# ExpansionHub.net
KiCad netlist of a schematic drawn in EAGLE
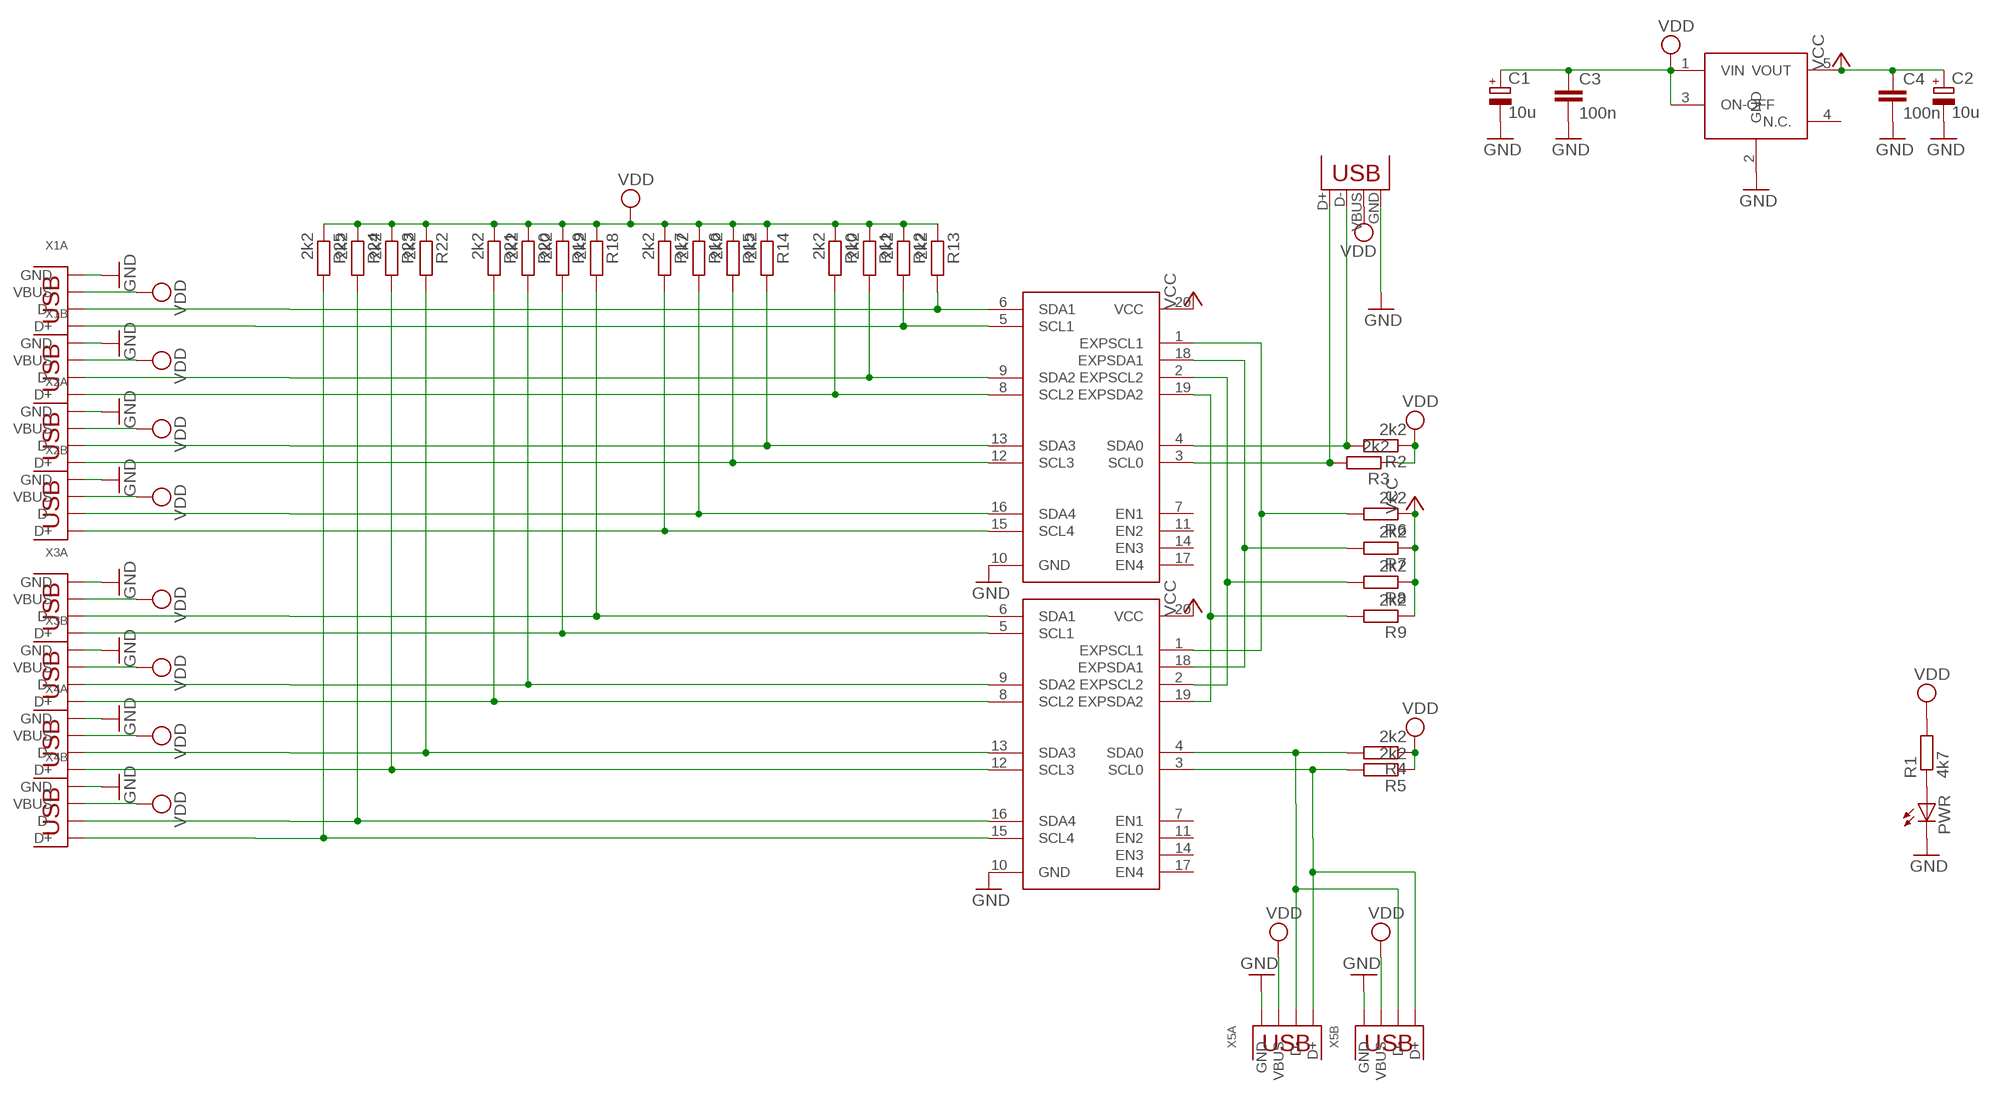
[diagram p0: schematic, sheet 1]

(export (version "E")
  (design (tool "Eeschema 10.0.6"))
  (components
    (comp (ref "C1")
      (value "10u")
      (footprint "eagle-import:A_3216-18W")
      (libsource (lib "eagle-import") (part "CPOL-EUA/3216-18W"))
    )
    (comp (ref "C2")
      (value "10u")
      (footprint "eagle-import:A_3216-18W")
      (libsource (lib "eagle-import") (part "CPOL-EUA/3216-18W"))
    )
    (comp (ref "C3")
      (value "100n")
      (footprint "eagle-import:C0805")
      (libsource (lib "eagle-import") (part "C-EUC0805"))
    )
    (comp (ref "C4")
      (value "100n")
      (footprint "eagle-import:C0805")
      (libsource (lib "eagle-import") (part "C-EUC0805"))
    )
    (comp (ref "IC1")
      (value "PCA9518")
      (footprint "eagle-import:TSSOP20")
      (libsource (lib "eagle-import") (part "PCA9518"))
    )
    (comp (ref "IC2")
      (value "PCA9518")
      (footprint "eagle-import:TSSOP20")
      (libsource (lib "eagle-import") (part "PCA9518"))
    )
    (comp (ref "PWR")
      (value "LED3MM")
      (footprint "eagle-import:LED3MM")
      (libsource (lib "eagle-import") (part "LED3MM"))
    )
    (comp (ref "R1")
      (value "4k7")
      (footprint "eagle-import:R0805W")
      (libsource (lib "eagle-import") (part "R-EU_R0805W"))
    )
    (comp (ref "R2")
      (value "2k2")
      (footprint "eagle-import:R0805")
      (libsource (lib "eagle-import") (part "R-EU_R0805"))
    )
    (comp (ref "R3")
      (value "2k2")
      (footprint "eagle-import:R0805")
      (libsource (lib "eagle-import") (part "R-EU_R0805"))
    )
    (comp (ref "R4")
      (value "2k2")
      (footprint "eagle-import:R0805")
      (libsource (lib "eagle-import") (part "R-EU_R0805"))
    )
    (comp (ref "R5")
      (value "2k2")
      (footprint "eagle-import:R0805")
      (libsource (lib "eagle-import") (part "R-EU_R0805"))
    )
    (comp (ref "R6")
      (value "2k2")
      (footprint "eagle-import:R0805")
      (libsource (lib "eagle-import") (part "R-EU_R0805"))
    )
    (comp (ref "R7")
      (value "2k2")
      (footprint "eagle-import:R0805")
      (libsource (lib "eagle-import") (part "R-EU_R0805"))
    )
    (comp (ref "R8")
      (value "2k2")
      (footprint "eagle-import:R0805")
      (libsource (lib "eagle-import") (part "R-EU_R0805"))
    )
    (comp (ref "R9")
      (value "2k2")
      (footprint "eagle-import:R0805")
      (libsource (lib "eagle-import") (part "R-EU_R0805"))
    )
    (comp (ref "R10")
      (value "2k2")
      (footprint "eagle-import:R0805")
      (libsource (lib "eagle-import") (part "R-EU_R0805"))
    )
    (comp (ref "R11")
      (value "2k2")
      (footprint "eagle-import:R0805")
      (libsource (lib "eagle-import") (part "R-EU_R0805"))
    )
    (comp (ref "R12")
      (value "2k2")
      (footprint "eagle-import:R0805")
      (libsource (lib "eagle-import") (part "R-EU_R0805"))
    )
    (comp (ref "R13")
      (value "2k2")
      (footprint "eagle-import:R0805")
      (libsource (lib "eagle-import") (part "R-EU_R0805"))
    )
    (comp (ref "R14")
      (value "2k2")
      (footprint "eagle-import:R0805")
      (libsource (lib "eagle-import") (part "R-EU_R0805"))
    )
    (comp (ref "R15")
      (value "2k2")
      (footprint "eagle-import:R0805")
      (libsource (lib "eagle-import") (part "R-EU_R0805"))
    )
    (comp (ref "R16")
      (value "2k2")
      (footprint "eagle-import:R0805")
      (libsource (lib "eagle-import") (part "R-EU_R0805"))
    )
    (comp (ref "R17")
      (value "2k2")
      (footprint "eagle-import:R0805")
      (libsource (lib "eagle-import") (part "R-EU_R0805"))
    )
    (comp (ref "R18")
      (value "2k2")
      (footprint "eagle-import:R0805")
      (libsource (lib "eagle-import") (part "R-EU_R0805"))
    )
    (comp (ref "R19")
      (value "2k2")
      (footprint "eagle-import:R0805")
      (libsource (lib "eagle-import") (part "R-EU_R0805"))
    )
    (comp (ref "R20")
      (value "2k2")
      (footprint "eagle-import:R0805")
      (libsource (lib "eagle-import") (part "R-EU_R0805"))
    )
    (comp (ref "R21")
      (value "2k2")
      (footprint "eagle-import:R0805")
      (libsource (lib "eagle-import") (part "R-EU_R0805"))
    )
    (comp (ref "R22")
      (value "2k2")
      (footprint "eagle-import:R0805")
      (libsource (lib "eagle-import") (part "R-EU_R0805"))
    )
    (comp (ref "R23")
      (value "2k2")
      (footprint "eagle-import:R0805")
      (libsource (lib "eagle-import") (part "R-EU_R0805"))
    )
    (comp (ref "R24")
      (value "2k2")
      (footprint "eagle-import:R0805")
      (libsource (lib "eagle-import") (part "R-EU_R0805"))
    )
    (comp (ref "R25")
      (value "2k2")
      (footprint "eagle-import:R0805")
      (libsource (lib "eagle-import") (part "R-EU_R0805"))
    )
    (comp (ref "U1")
      (value "LP2985")
      (footprint "eagle-import:SOT23-5")
      (libsource (lib "eagle-import") (part "LP2985"))
    )
    (comp (ref "X1")
      (value "DUA-USB")
      (footprint "eagle-import:DUAL")
      (libsource (lib "eagle-import") (part "DUA-USB"))
    )
    (comp (ref "X2")
      (value "DUA-USB")
      (footprint "eagle-import:DUAL")
      (libsource (lib "eagle-import") (part "DUA-USB"))
    )
    (comp (ref "X3")
      (value "DUA-USB")
      (footprint "eagle-import:DUAL")
      (libsource (lib "eagle-import") (part "DUA-USB"))
    )
    (comp (ref "X4")
      (value "DUA-USB")
      (footprint "eagle-import:DUAL")
      (libsource (lib "eagle-import") (part "DUA-USB"))
    )
    (comp (ref "X5")
      (value "DUA-USB")
      (footprint "eagle-import:DUAL")
      (libsource (lib "eagle-import") (part "DUA-USB"))
    )
    (comp (ref "X11")
      (value "USBSMD")
      (footprint "eagle-import:USB-MINIB")
      (libsource (lib "eagle-import") (part "USBSMD"))
    )
  )
  (nets
    (net (code "1") (name "GND") (class "Default")
      (node (ref "C1") (pin "-") (pinfunction "-_-") (pintype "passive"))
      (node (ref "C2") (pin "-") (pinfunction "-_-") (pintype "passive"))
      (node (ref "C3") (pin "2") (pinfunction "2_2") (pintype "passive"))
      (node (ref "C4") (pin "2") (pinfunction "2_2") (pintype "passive"))
      (node (ref "IC1") (pin "10") (pinfunction "GND_10") (pintype "bidirectional"))
      (node (ref "IC2") (pin "10") (pinfunction "GND_10") (pintype "bidirectional"))
      (node (ref "PWR") (pin "K") (pinfunction "C_K") (pintype "passive"))
      (node (ref "U1") (pin "2") (pinfunction "GND_2") (pintype "bidirectional"))
      (node (ref "X1") (pin "1-4") (pinfunction "GND_1-4") (pintype "bidirectional"))
      (node (ref "X1") (pin "2-4") (pinfunction "GND_2-4") (pintype "bidirectional"))
      (node (ref "X11") (pin "GND") (pinfunction "GND_GND") (pintype "bidirectional"))
      (node (ref "X2") (pin "1-4") (pinfunction "GND_1-4") (pintype "bidirectional"))
      (node (ref "X2") (pin "2-4") (pinfunction "GND_2-4") (pintype "bidirectional"))
      (node (ref "X3") (pin "1-4") (pinfunction "GND_1-4") (pintype "bidirectional"))
      (node (ref "X3") (pin "2-4") (pinfunction "GND_2-4") (pintype "bidirectional"))
      (node (ref "X4") (pin "1-4") (pinfunction "GND_1-4") (pintype "bidirectional"))
      (node (ref "X4") (pin "2-4") (pinfunction "GND_2-4") (pintype "bidirectional"))
      (node (ref "X5") (pin "1-4") (pinfunction "GND_1-4") (pintype "bidirectional"))
      (node (ref "X5") (pin "2-4") (pinfunction "GND_2-4") (pintype "bidirectional"))
    )
    (net (code "2") (name "Net-(IC1-EXPSCL1)") (class "Default")
      (node (ref "IC1") (pin "1") (pinfunction "EXPSCL1_1") (pintype "bidirectional"))
      (node (ref "IC2") (pin "1") (pinfunction "EXPSCL1_1") (pintype "bidirectional"))
      (node (ref "R6") (pin "2") (pinfunction "2_2") (pintype "passive"))
    )
    (net (code "3") (name "Net-(IC1-EXPSCL2)") (class "Default")
      (node (ref "IC1") (pin "2") (pinfunction "EXPSCL2_2") (pintype "bidirectional"))
      (node (ref "IC2") (pin "2") (pinfunction "EXPSCL2_2") (pintype "bidirectional"))
      (node (ref "R8") (pin "2") (pinfunction "2_2") (pintype "passive"))
    )
    (net (code "4") (name "Net-(IC1-EXPSDA1)") (class "Default")
      (node (ref "IC1") (pin "18") (pinfunction "EXPSDA1_18") (pintype "bidirectional"))
      (node (ref "IC2") (pin "18") (pinfunction "EXPSDA1_18") (pintype "bidirectional"))
      (node (ref "R7") (pin "2") (pinfunction "2_2") (pintype "passive"))
    )
    (net (code "5") (name "Net-(IC1-EXPSDA2)") (class "Default")
      (node (ref "IC1") (pin "19") (pinfunction "EXPSDA2_19") (pintype "bidirectional"))
      (node (ref "IC2") (pin "19") (pinfunction "EXPSDA2_19") (pintype "bidirectional"))
      (node (ref "R9") (pin "2") (pinfunction "2_2") (pintype "passive"))
    )
    (net (code "6") (name "Net-(IC1-SCL0)") (class "Default")
      (node (ref "IC1") (pin "3") (pinfunction "SCL0_3") (pintype "bidirectional"))
      (node (ref "R3") (pin "2") (pinfunction "2_2") (pintype "passive"))
      (node (ref "X11") (pin "D+") (pinfunction "D+_D+") (pintype "bidirectional"))
    )
    (net (code "7") (name "Net-(IC1-SCL1)") (class "Default")
      (node (ref "IC1") (pin "5") (pinfunction "SCL1_5") (pintype "bidirectional"))
      (node (ref "R12") (pin "2") (pinfunction "2_2") (pintype "passive"))
      (node (ref "X1") (pin "1-3") (pinfunction "D+_1-3") (pintype "bidirectional"))
    )
    (net (code "8") (name "Net-(IC1-SCL2)") (class "Default")
      (node (ref "IC1") (pin "8") (pinfunction "SCL2_8") (pintype "bidirectional"))
      (node (ref "R10") (pin "2") (pinfunction "2_2") (pintype "passive"))
      (node (ref "X1") (pin "2-3") (pinfunction "D+_2-3") (pintype "bidirectional"))
    )
    (net (code "9") (name "Net-(IC1-SCL3)") (class "Default")
      (node (ref "IC1") (pin "12") (pinfunction "SCL3_12") (pintype "bidirectional"))
      (node (ref "R15") (pin "2") (pinfunction "2_2") (pintype "passive"))
      (node (ref "X2") (pin "1-3") (pinfunction "D+_1-3") (pintype "bidirectional"))
    )
    (net (code "10") (name "Net-(IC1-SCL4)") (class "Default")
      (node (ref "IC1") (pin "15") (pinfunction "SCL4_15") (pintype "bidirectional"))
      (node (ref "R17") (pin "2") (pinfunction "2_2") (pintype "passive"))
      (node (ref "X2") (pin "2-3") (pinfunction "D+_2-3") (pintype "bidirectional"))
    )
    (net (code "11") (name "Net-(IC1-SDA0)") (class "Default")
      (node (ref "IC1") (pin "4") (pinfunction "SDA0_4") (pintype "bidirectional"))
      (node (ref "R2") (pin "2") (pinfunction "2_2") (pintype "passive"))
      (node (ref "X11") (pin "D-") (pinfunction "D-_D-") (pintype "bidirectional"))
    )
    (net (code "12") (name "Net-(IC1-SDA1)") (class "Default")
      (node (ref "IC1") (pin "6") (pinfunction "SDA1_6") (pintype "bidirectional"))
      (node (ref "R13") (pin "2") (pinfunction "2_2") (pintype "passive"))
      (node (ref "X1") (pin "1-2") (pinfunction "D-_1-2") (pintype "bidirectional"))
    )
    (net (code "13") (name "Net-(IC1-SDA2)") (class "Default")
      (node (ref "IC1") (pin "9") (pinfunction "SDA2_9") (pintype "bidirectional"))
      (node (ref "R11") (pin "2") (pinfunction "2_2") (pintype "passive"))
      (node (ref "X1") (pin "2-2") (pinfunction "D-_2-2") (pintype "bidirectional"))
    )
    (net (code "14") (name "Net-(IC1-SDA3)") (class "Default")
      (node (ref "IC1") (pin "13") (pinfunction "SDA3_13") (pintype "bidirectional"))
      (node (ref "R14") (pin "2") (pinfunction "2_2") (pintype "passive"))
      (node (ref "X2") (pin "1-2") (pinfunction "D-_1-2") (pintype "bidirectional"))
    )
    (net (code "15") (name "Net-(IC1-SDA4)") (class "Default")
      (node (ref "IC1") (pin "16") (pinfunction "SDA4_16") (pintype "bidirectional"))
      (node (ref "R16") (pin "2") (pinfunction "2_2") (pintype "passive"))
      (node (ref "X2") (pin "2-2") (pinfunction "D-_2-2") (pintype "bidirectional"))
    )
    (net (code "16") (name "Net-(IC2-SCL0)") (class "Default")
      (node (ref "IC2") (pin "3") (pinfunction "SCL0_3") (pintype "bidirectional"))
      (node (ref "R5") (pin "2") (pinfunction "2_2") (pintype "passive"))
      (node (ref "X5") (pin "1-3") (pinfunction "D+_1-3") (pintype "bidirectional"))
      (node (ref "X5") (pin "2-3") (pinfunction "D+_2-3") (pintype "bidirectional"))
    )
    (net (code "17") (name "Net-(IC2-SCL1)") (class "Default")
      (node (ref "IC2") (pin "5") (pinfunction "SCL1_5") (pintype "bidirectional"))
      (node (ref "R19") (pin "2") (pinfunction "2_2") (pintype "passive"))
      (node (ref "X3") (pin "1-3") (pinfunction "D+_1-3") (pintype "bidirectional"))
    )
    (net (code "18") (name "Net-(IC2-SCL2)") (class "Default")
      (node (ref "IC2") (pin "8") (pinfunction "SCL2_8") (pintype "bidirectional"))
      (node (ref "R21") (pin "2") (pinfunction "2_2") (pintype "passive"))
      (node (ref "X3") (pin "2-3") (pinfunction "D+_2-3") (pintype "bidirectional"))
    )
    (net (code "19") (name "Net-(IC2-SCL3)") (class "Default")
      (node (ref "IC2") (pin "12") (pinfunction "SCL3_12") (pintype "bidirectional"))
      (node (ref "R23") (pin "2") (pinfunction "2_2") (pintype "passive"))
      (node (ref "X4") (pin "1-3") (pinfunction "D+_1-3") (pintype "bidirectional"))
    )
    (net (code "20") (name "Net-(IC2-SCL4)") (class "Default")
      (node (ref "IC2") (pin "15") (pinfunction "SCL4_15") (pintype "bidirectional"))
      (node (ref "R25") (pin "2") (pinfunction "2_2") (pintype "passive"))
      (node (ref "X4") (pin "2-3") (pinfunction "D+_2-3") (pintype "bidirectional"))
    )
    (net (code "21") (name "Net-(IC2-SDA0)") (class "Default")
      (node (ref "IC2") (pin "4") (pinfunction "SDA0_4") (pintype "bidirectional"))
      (node (ref "R4") (pin "2") (pinfunction "2_2") (pintype "passive"))
      (node (ref "X5") (pin "1-2") (pinfunction "D-_1-2") (pintype "bidirectional"))
      (node (ref "X5") (pin "2-2") (pinfunction "D-_2-2") (pintype "bidirectional"))
    )
    (net (code "22") (name "Net-(IC2-SDA1)") (class "Default")
      (node (ref "IC2") (pin "6") (pinfunction "SDA1_6") (pintype "bidirectional"))
      (node (ref "R18") (pin "2") (pinfunction "2_2") (pintype "passive"))
      (node (ref "X3") (pin "1-2") (pinfunction "D-_1-2") (pintype "bidirectional"))
    )
    (net (code "23") (name "Net-(IC2-SDA2)") (class "Default")
      (node (ref "IC2") (pin "9") (pinfunction "SDA2_9") (pintype "bidirectional"))
      (node (ref "R20") (pin "2") (pinfunction "2_2") (pintype "passive"))
      (node (ref "X3") (pin "2-2") (pinfunction "D-_2-2") (pintype "bidirectional"))
    )
    (net (code "24") (name "Net-(IC2-SDA3)") (class "Default")
      (node (ref "IC2") (pin "13") (pinfunction "SDA3_13") (pintype "bidirectional"))
      (node (ref "R22") (pin "2") (pinfunction "2_2") (pintype "passive"))
      (node (ref "X4") (pin "1-2") (pinfunction "D-_1-2") (pintype "bidirectional"))
    )
    (net (code "25") (name "Net-(IC2-SDA4)") (class "Default")
      (node (ref "IC2") (pin "16") (pinfunction "SDA4_16") (pintype "bidirectional"))
      (node (ref "R24") (pin "2") (pinfunction "2_2") (pintype "passive"))
      (node (ref "X4") (pin "2-2") (pinfunction "D-_2-2") (pintype "bidirectional"))
    )
    (net (code "26") (name "Net-(PWR-PadA)") (class "Default")
      (node (ref "PWR") (pin "A") (pinfunction "A_A") (pintype "passive"))
      (node (ref "R1") (pin "1") (pinfunction "1_1") (pintype "passive"))
    )
    (net (code "27") (name "VCC") (class "Default")
      (node (ref "C2") (pin "+") (pinfunction "+_+") (pintype "passive"))
      (node (ref "C4") (pin "1") (pinfunction "1_1") (pintype "passive"))
      (node (ref "IC1") (pin "20") (pinfunction "VCC_20") (pintype "bidirectional"))
      (node (ref "IC2") (pin "20") (pinfunction "VCC_20") (pintype "bidirectional"))
      (node (ref "R6") (pin "1") (pinfunction "1_1") (pintype "passive"))
      (node (ref "R7") (pin "1") (pinfunction "1_1") (pintype "passive"))
      (node (ref "R8") (pin "1") (pinfunction "1_1") (pintype "passive"))
      (node (ref "R9") (pin "1") (pinfunction "1_1") (pintype "passive"))
      (node (ref "U1") (pin "5") (pinfunction "VOUT_5") (pintype "bidirectional"))
    )
    (net (code "28") (name "VDD") (class "Default")
      (node (ref "C1") (pin "+") (pinfunction "+_+") (pintype "passive"))
      (node (ref "C3") (pin "1") (pinfunction "1_1") (pintype "passive"))
      (node (ref "R1") (pin "2") (pinfunction "2_2") (pintype "passive"))
      (node (ref "R10") (pin "1") (pinfunction "1_1") (pintype "passive"))
      (node (ref "R11") (pin "1") (pinfunction "1_1") (pintype "passive"))
      (node (ref "R12") (pin "1") (pinfunction "1_1") (pintype "passive"))
      (node (ref "R13") (pin "1") (pinfunction "1_1") (pintype "passive"))
      (node (ref "R14") (pin "1") (pinfunction "1_1") (pintype "passive"))
      (node (ref "R15") (pin "1") (pinfunction "1_1") (pintype "passive"))
      (node (ref "R16") (pin "1") (pinfunction "1_1") (pintype "passive"))
      (node (ref "R17") (pin "1") (pinfunction "1_1") (pintype "passive"))
      (node (ref "R18") (pin "1") (pinfunction "1_1") (pintype "passive"))
      (node (ref "R19") (pin "1") (pinfunction "1_1") (pintype "passive"))
      (node (ref "R2") (pin "1") (pinfunction "1_1") (pintype "passive"))
      (node (ref "R20") (pin "1") (pinfunction "1_1") (pintype "passive"))
      (node (ref "R21") (pin "1") (pinfunction "1_1") (pintype "passive"))
      (node (ref "R22") (pin "1") (pinfunction "1_1") (pintype "passive"))
      (node (ref "R23") (pin "1") (pinfunction "1_1") (pintype "passive"))
      (node (ref "R24") (pin "1") (pinfunction "1_1") (pintype "passive"))
      (node (ref "R25") (pin "1") (pinfunction "1_1") (pintype "passive"))
      (node (ref "R3") (pin "1") (pinfunction "1_1") (pintype "passive"))
      (node (ref "R4") (pin "1") (pinfunction "1_1") (pintype "passive"))
      (node (ref "R5") (pin "1") (pinfunction "1_1") (pintype "passive"))
      (node (ref "U1") (pin "1") (pinfunction "VIN_1") (pintype "bidirectional"))
      (node (ref "U1") (pin "3") (pinfunction "ON-OFF_3") (pintype "bidirectional"))
      (node (ref "X1") (pin "1-1") (pinfunction "VBUS_1-1") (pintype "bidirectional"))
      (node (ref "X1") (pin "2-1") (pinfunction "VBUS_2-1") (pintype "bidirectional"))
      (node (ref "X11") (pin "VBUS") (pinfunction "VBUS_VBUS") (pintype "bidirectional"))
      (node (ref "X2") (pin "1-1") (pinfunction "VBUS_1-1") (pintype "bidirectional"))
      (node (ref "X2") (pin "2-1") (pinfunction "VBUS_2-1") (pintype "bidirectional"))
      (node (ref "X3") (pin "1-1") (pinfunction "VBUS_1-1") (pintype "bidirectional"))
      (node (ref "X3") (pin "2-1") (pinfunction "VBUS_2-1") (pintype "bidirectional"))
      (node (ref "X4") (pin "1-1") (pinfunction "VBUS_1-1") (pintype "bidirectional"))
      (node (ref "X4") (pin "2-1") (pinfunction "VBUS_2-1") (pintype "bidirectional"))
      (node (ref "X5") (pin "1-1") (pinfunction "VBUS_1-1") (pintype "bidirectional"))
      (node (ref "X5") (pin "2-1") (pinfunction "VBUS_2-1") (pintype "bidirectional"))
    )
    (net (code "29") (name "unconnected-(IC1-EN1-Pad7)") (class "Default")
      (node (ref "IC1") (pin "7") (pinfunction "EN1_7") (pintype "bidirectional"))
    )
    (net (code "30") (name "unconnected-(IC1-EN2-Pad11)") (class "Default")
      (node (ref "IC1") (pin "11") (pinfunction "EN2_11") (pintype "bidirectional"))
    )
    (net (code "31") (name "unconnected-(IC1-EN3-Pad14)") (class "Default")
      (node (ref "IC1") (pin "14") (pinfunction "EN3_14") (pintype "bidirectional"))
    )
    (net (code "32") (name "unconnected-(IC1-EN4-Pad17)") (class "Default")
      (node (ref "IC1") (pin "17") (pinfunction "EN4_17") (pintype "bidirectional"))
    )
    (net (code "33") (name "unconnected-(IC2-EN1-Pad7)") (class "Default")
      (node (ref "IC2") (pin "7") (pinfunction "EN1_7") (pintype "bidirectional"))
    )
    (net (code "34") (name "unconnected-(IC2-EN2-Pad11)") (class "Default")
      (node (ref "IC2") (pin "11") (pinfunction "EN2_11") (pintype "bidirectional"))
    )
    (net (code "35") (name "unconnected-(IC2-EN3-Pad14)") (class "Default")
      (node (ref "IC2") (pin "14") (pinfunction "EN3_14") (pintype "bidirectional"))
    )
    (net (code "36") (name "unconnected-(IC2-EN4-Pad17)") (class "Default")
      (node (ref "IC2") (pin "17") (pinfunction "EN4_17") (pintype "bidirectional"))
    )
    (net (code "37") (name "unconnected-(U1-N.C.-Pad4)") (class "Default")
      (node (ref "U1") (pin "4") (pinfunction "N.C._4") (pintype "bidirectional"))
    )
  )
)
